# Pro_Trinket_Keyboard_V3_2.net
KiCad netlist of a schematic drawn in EAGLE
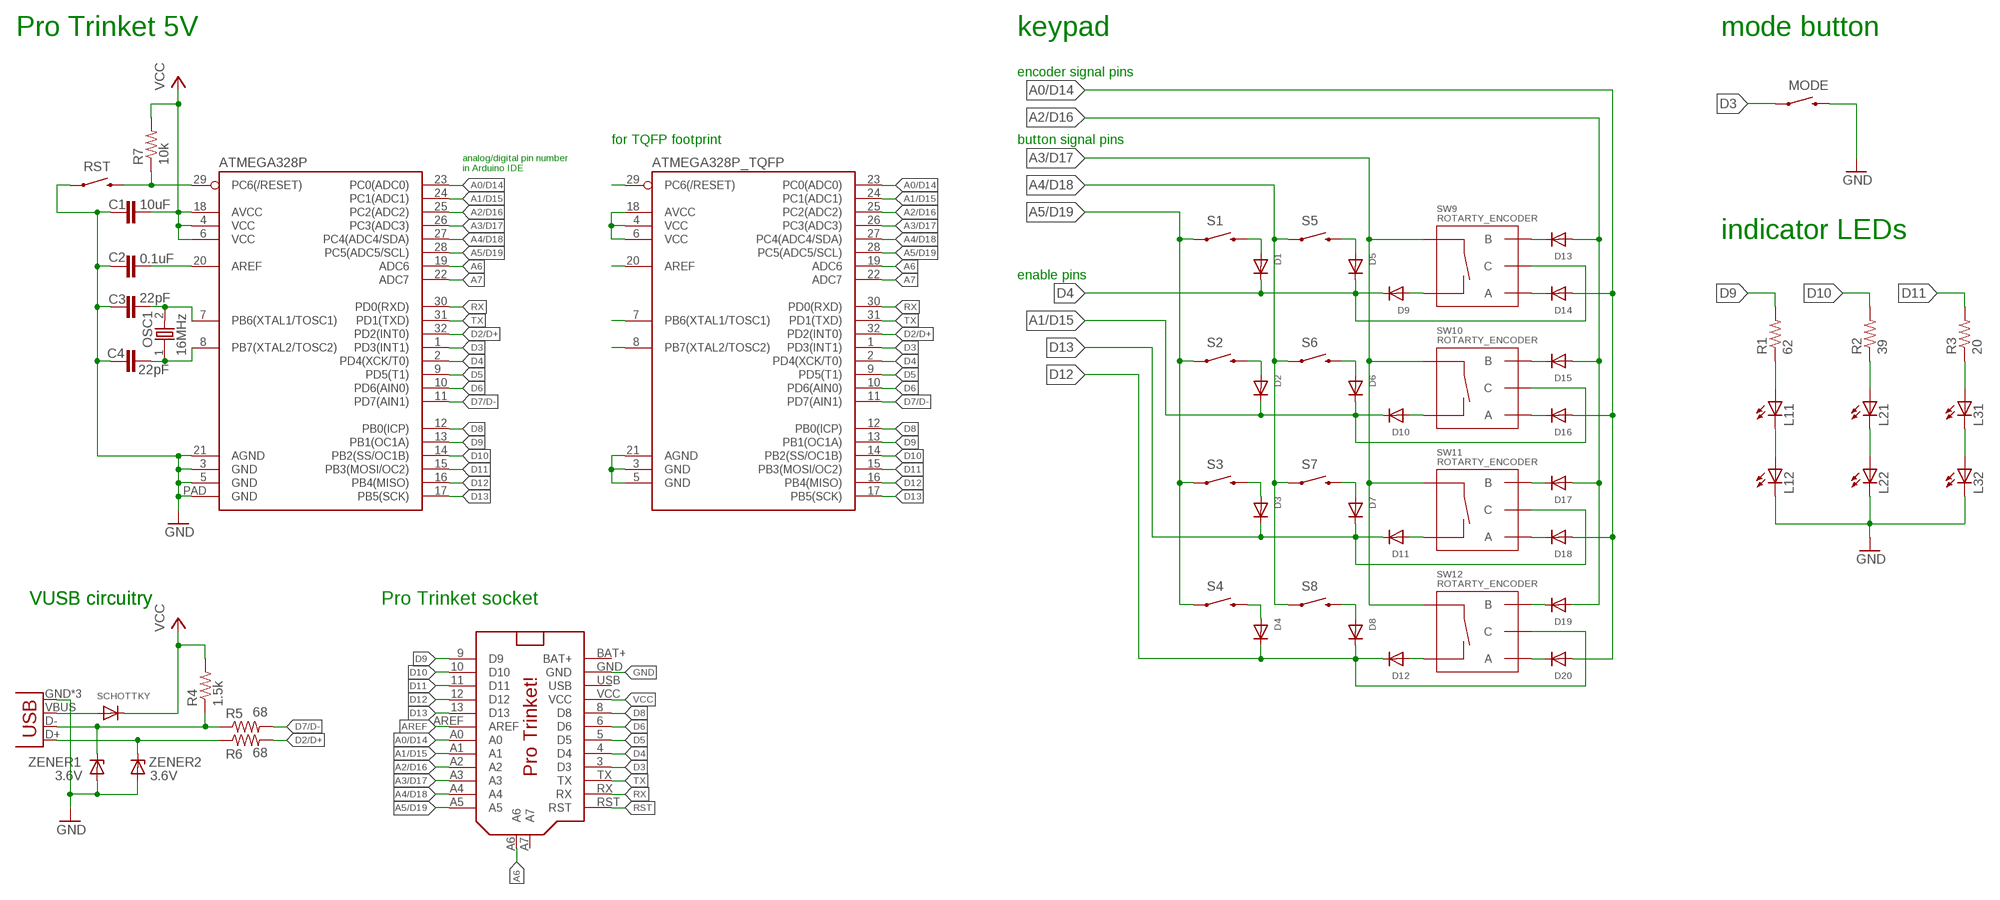
[diagram p0: schematic, sheet 1]

(export (version "E")
  (design (tool "Eeschema 10.0.6"))
  (components
    (comp (ref "ATMEGA328P")
      (value "ATMEGA328P_MLFMLF32")
      (footprint "eagle-import:MLF32-PAD")
      (libsource (lib "eagle-import") (part "ATMEGA328P_MLFMLF32"))
    )
    (comp (ref "ATMEGA328P_TQFP")
      (value "ATMEGA328P_TQFP")
      (footprint "eagle-import:TQFP32-08")
      (libsource (lib "eagle-import") (part "ATMEGA328P_TQFP"))
    )
    (comp (ref "C1")
      (value "10uF")
      (footprint "eagle-import:0603-CAP")
      (libsource (lib "eagle-import") (part "10UF-6.3V-20%(0603)"))
    )
    (comp (ref "C2")
      (value "0.1uF")
      (footprint "eagle-import:0603-CAP")
      (libsource (lib "eagle-import") (part "22PF-50V-5%(0603)"))
    )
    (comp (ref "C3")
      (value "22pF")
      (footprint "eagle-import:0603-CAP")
      (libsource (lib "eagle-import") (part "22PF-50V-5%(0603)"))
    )
    (comp (ref "C4")
      (value "22pF")
      (footprint "eagle-import:0603-CAP")
      (libsource (lib "eagle-import") (part "22PF-50V-5%(0603)"))
    )
    (comp (ref "D1")
      (value "DIODESOD-123")
      (footprint "eagle-import:SOD-123")
      (libsource (lib "eagle-import") (part "DIODESOD-123"))
    )
    (comp (ref "D2")
      (value "DIODESOD-123")
      (footprint "eagle-import:SOD-123")
      (libsource (lib "eagle-import") (part "DIODESOD-123"))
    )
    (comp (ref "D3")
      (value "DIODESOD-123")
      (footprint "eagle-import:SOD-123")
      (libsource (lib "eagle-import") (part "DIODESOD-123"))
    )
    (comp (ref "D4")
      (value "DIODESOD-123")
      (footprint "eagle-import:SOD-123")
      (libsource (lib "eagle-import") (part "DIODESOD-123"))
    )
    (comp (ref "D5")
      (value "DIODESOD-123")
      (footprint "eagle-import:SOD-123")
      (libsource (lib "eagle-import") (part "DIODESOD-123"))
    )
    (comp (ref "D6")
      (value "DIODESOD-123")
      (footprint "eagle-import:SOD-123")
      (libsource (lib "eagle-import") (part "DIODESOD-123"))
    )
    (comp (ref "D7")
      (value "DIODESOD-123")
      (footprint "eagle-import:SOD-123")
      (libsource (lib "eagle-import") (part "DIODESOD-123"))
    )
    (comp (ref "D8")
      (value "DIODESOD-123")
      (footprint "eagle-import:SOD-123")
      (libsource (lib "eagle-import") (part "DIODESOD-123"))
    )
    (comp (ref "D9")
      (value "DIODESOD-123")
      (footprint "eagle-import:SOD-123")
      (libsource (lib "eagle-import") (part "DIODESOD-123"))
    )
    (comp (ref "D10")
      (value "DIODESOD-123")
      (footprint "eagle-import:SOD-123")
      (libsource (lib "eagle-import") (part "DIODESOD-123"))
    )
    (comp (ref "D11")
      (value "DIODESOD-123")
      (footprint "eagle-import:SOD-123")
      (libsource (lib "eagle-import") (part "DIODESOD-123"))
    )
    (comp (ref "D12")
      (value "DIODESOD-123")
      (footprint "eagle-import:SOD-123")
      (libsource (lib "eagle-import") (part "DIODESOD-123"))
    )
    (comp (ref "D13")
      (value "DIODESOD-123")
      (footprint "eagle-import:SOD-123")
      (libsource (lib "eagle-import") (part "DIODESOD-123"))
    )
    (comp (ref "D14")
      (value "DIODESOD-123")
      (footprint "eagle-import:SOD-123")
      (libsource (lib "eagle-import") (part "DIODESOD-123"))
    )
    (comp (ref "D15")
      (value "DIODESOD-123")
      (footprint "eagle-import:SOD-123")
      (libsource (lib "eagle-import") (part "DIODESOD-123"))
    )
    (comp (ref "D16")
      (value "DIODESOD-123")
      (footprint "eagle-import:SOD-123")
      (libsource (lib "eagle-import") (part "DIODESOD-123"))
    )
    (comp (ref "D17")
      (value "DIODESOD-123")
      (footprint "eagle-import:SOD-123")
      (libsource (lib "eagle-import") (part "DIODESOD-123"))
    )
    (comp (ref "D18")
      (value "DIODESOD-123")
      (footprint "eagle-import:SOD-123")
      (libsource (lib "eagle-import") (part "DIODESOD-123"))
    )
    (comp (ref "D19")
      (value "DIODESOD-123")
      (footprint "eagle-import:SOD-123")
      (libsource (lib "eagle-import") (part "DIODESOD-123"))
    )
    (comp (ref "D20")
      (value "DIODESOD-123")
      (footprint "eagle-import:SOD-123")
      (libsource (lib "eagle-import") (part "DIODESOD-123"))
    )
    (comp (ref "JP1")
      (value "USB-MICROB")
      (footprint "eagle-import:USB-MICROB")
      (libsource (lib "eagle-import") (part "USB-MICROB"))
    )
    (comp (ref "L11")
      (value "LEDCHIPLED_0805")
      (footprint "eagle-import:CHIPLED_0805")
      (libsource (lib "eagle-import") (part "LEDCHIPLED_0805"))
    )
    (comp (ref "L12")
      (value "LEDCHIPLED_0805")
      (footprint "eagle-import:CHIPLED_0805")
      (libsource (lib "eagle-import") (part "LEDCHIPLED_0805"))
    )
    (comp (ref "L21")
      (value "LEDCHIPLED_0805")
      (footprint "eagle-import:CHIPLED_0805")
      (libsource (lib "eagle-import") (part "LEDCHIPLED_0805"))
    )
    (comp (ref "L22")
      (value "LEDCHIPLED_0805")
      (footprint "eagle-import:CHIPLED_0805")
      (libsource (lib "eagle-import") (part "LEDCHIPLED_0805"))
    )
    (comp (ref "L31")
      (value "LEDCHIPLED_0805")
      (footprint "eagle-import:CHIPLED_0805")
      (libsource (lib "eagle-import") (part "LEDCHIPLED_0805"))
    )
    (comp (ref "L32")
      (value "LEDCHIPLED_0805")
      (footprint "eagle-import:CHIPLED_0805")
      (libsource (lib "eagle-import") (part "LEDCHIPLED_0805"))
    )
    (comp (ref "MODE")
      (value "SWITCH-MOMENTARY-2SIDE_EZ")
      (footprint "eagle-import:TACTILE-PTH-SIDEEZ")
      (libsource (lib "eagle-import") (part "SWITCH-MOMENTARY-2SIDE_EZ"))
    )
    (comp (ref "OSC1")
      (value "16MHz")
      (footprint "eagle-import:HC-49U")
      (libsource (lib "eagle-import") (part "OSC-XTAL-HC-49U-SMD"))
    )
    (comp (ref "R1")
      (value "62")
      (footprint "eagle-import:M0805")
      (libsource (lib "eagle-import") (part "R-US_M0805"))
    )
    (comp (ref "R2")
      (value "39")
      (footprint "eagle-import:M0805")
      (libsource (lib "eagle-import") (part "R-US_M0805"))
    )
    (comp (ref "R3")
      (value "20")
      (footprint "eagle-import:M0805")
      (libsource (lib "eagle-import") (part "R-US_M0805"))
    )
    (comp (ref "R4")
      (value "1.5k")
      (footprint "eagle-import:0805")
      (libsource (lib "eagle-import") (part "RESISTOR0805-RES"))
    )
    (comp (ref "R5")
      (value "68")
      (footprint "eagle-import:0805")
      (libsource (lib "eagle-import") (part "RESISTOR0805-RES"))
    )
    (comp (ref "R6")
      (value "68")
      (footprint "eagle-import:0805")
      (libsource (lib "eagle-import") (part "RESISTOR0805-RES"))
    )
    (comp (ref "R7")
      (value "10k")
      (footprint "eagle-import:0805")
      (libsource (lib "eagle-import") (part "RESISTOR0805-RES"))
    )
    (comp (ref "RST")
      (value "SWITCH-MOMENTARY-2SIDE_EZ")
      (footprint "eagle-import:TACTILE-PTH-SIDEEZ")
      (libsource (lib "eagle-import") (part "SWITCH-MOMENTARY-2SIDE_EZ"))
    )
    (comp (ref "S1")
      (value "SWITCH-MOMENTARY-212MM")
      (footprint "eagle-import:TACTILE-PTH-12MM")
      (libsource (lib "eagle-import") (part "SWITCH-MOMENTARY-212MM"))
    )
    (comp (ref "S2")
      (value "SWITCH-MOMENTARY-212MM")
      (footprint "eagle-import:TACTILE-PTH-12MM")
      (libsource (lib "eagle-import") (part "SWITCH-MOMENTARY-212MM"))
    )
    (comp (ref "S3")
      (value "SWITCH-MOMENTARY-212MM")
      (footprint "eagle-import:TACTILE-PTH-12MM")
      (libsource (lib "eagle-import") (part "SWITCH-MOMENTARY-212MM"))
    )
    (comp (ref "S4")
      (value "SWITCH-MOMENTARY-212MM")
      (footprint "eagle-import:TACTILE-PTH-12MM")
      (libsource (lib "eagle-import") (part "SWITCH-MOMENTARY-212MM"))
    )
    (comp (ref "S5")
      (value "SWITCH-MOMENTARY-212MM")
      (footprint "eagle-import:TACTILE-PTH-12MM")
      (libsource (lib "eagle-import") (part "SWITCH-MOMENTARY-212MM"))
    )
    (comp (ref "S6")
      (value "SWITCH-MOMENTARY-212MM")
      (footprint "eagle-import:TACTILE-PTH-12MM")
      (libsource (lib "eagle-import") (part "SWITCH-MOMENTARY-212MM"))
    )
    (comp (ref "S7")
      (value "SWITCH-MOMENTARY-212MM")
      (footprint "eagle-import:TACTILE-PTH-12MM")
      (libsource (lib "eagle-import") (part "SWITCH-MOMENTARY-212MM"))
    )
    (comp (ref "S8")
      (value "SWITCH-MOMENTARY-212MM")
      (footprint "eagle-import:TACTILE-PTH-12MM")
      (libsource (lib "eagle-import") (part "SWITCH-MOMENTARY-212MM"))
    )
    (comp (ref "SCHOTTKY")
      (value "DIODESMA")
      (footprint "eagle-import:SMADIODE")
      (libsource (lib "eagle-import") (part "DIODESMA"))
    )
    (comp (ref "SW9")
      (value "ROTARTY_ENCODER")
      (footprint "eagle-import:ROTARY_ENC_PLAIN")
      (libsource (lib "eagle-import") (part "ROTARTY_ENCODER"))
    )
    (comp (ref "SW10")
      (value "ROTARTY_ENCODER")
      (footprint "eagle-import:ROTARY_ENC_PLAIN")
      (libsource (lib "eagle-import") (part "ROTARTY_ENCODER"))
    )
    (comp (ref "SW11")
      (value "ROTARTY_ENCODER")
      (footprint "eagle-import:ROTARY_ENC_PLAIN")
      (libsource (lib "eagle-import") (part "ROTARTY_ENCODER"))
    )
    (comp (ref "SW12")
      (value "ROTARTY_ENCODER")
      (footprint "eagle-import:ROTARY_ENC_PLAIN")
      (libsource (lib "eagle-import") (part "ROTARTY_ENCODER"))
    )
    (comp (ref "U$2")
      (value "PRO_TRINKET")
      (footprint "eagle-import:PROTRINKET")
      (libsource (lib "eagle-import") (part "PRO_TRINKET"))
    )
    (comp (ref "ZENER1")
      (value "3.6V")
      (footprint "eagle-import:SOD80C")
      (libsource (lib "eagle-import") (part "ZENER-DIODESOD80C"))
    )
    (comp (ref "ZENER2")
      (value "3.6V")
      (footprint "eagle-import:SOD80C")
      (libsource (lib "eagle-import") (part "ZENER-DIODESOD80C"))
    )
  )
  (nets
    (net (code "1") (name "/BAT+") (class "Default")
      (node (ref "U$2") (pin "BAT+") (pinfunction "BAT+_BAT+") (pintype "power_in"))
    )
    (net (code "2") (name "/USB") (class "Default")
      (node (ref "U$2") (pin "USB") (pinfunction "USB_USB") (pintype "power_in"))
    )
    (net (code "3") (name "/XTAL1") (class "Default")
      (node (ref "ATMEGA328P") (pin "7") (pinfunction "PB6(XTAL1/TOSC1)_7") (pintype "bidirectional"))
      (node (ref "ATMEGA328P_TQFP") (pin "7") (pinfunction "PB6(XTAL1/TOSC1)_7") (pintype "bidirectional"))
      (node (ref "C3") (pin "2") (pinfunction "2_2") (pintype "passive"))
      (node (ref "OSC1") (pin "2") (pinfunction "2_2") (pintype "passive"))
    )
    (net (code "4") (name "/XTAL2") (class "Default")
      (node (ref "ATMEGA328P") (pin "8") (pinfunction "PB7(XTAL2/TOSC2)_8") (pintype "bidirectional"))
      (node (ref "ATMEGA328P_TQFP") (pin "8") (pinfunction "PB7(XTAL2/TOSC2)_8") (pintype "bidirectional"))
      (node (ref "C4") (pin "1") (pinfunction "1_1") (pintype "passive"))
      (node (ref "OSC1") (pin "1") (pinfunction "1_1") (pintype "passive"))
    )
    (net (code "5") (name "A0{slash}D14") (class "Default")
      (node (ref "ATMEGA328P") (pin "23") (pinfunction "PC0(ADC0)_23") (pintype "bidirectional"))
      (node (ref "ATMEGA328P_TQFP") (pin "23") (pinfunction "PC0(ADC0)_23") (pintype "bidirectional"))
      (node (ref "D14") (pin "A") (pinfunction "A_A") (pintype "passive"))
      (node (ref "D16") (pin "A") (pinfunction "A_A") (pintype "passive"))
      (node (ref "D18") (pin "A") (pinfunction "A_A") (pintype "passive"))
      (node (ref "D20") (pin "A") (pinfunction "A_A") (pintype "passive"))
      (node (ref "U$2") (pin "A0") (pinfunction "A0_A0") (pintype "bidirectional"))
    )
    (net (code "6") (name "A1{slash}D15") (class "Default")
      (node (ref "ATMEGA328P") (pin "24") (pinfunction "PC1(ADC1)_24") (pintype "bidirectional"))
      (node (ref "ATMEGA328P_TQFP") (pin "24") (pinfunction "PC1(ADC1)_24") (pintype "bidirectional"))
      (node (ref "D10") (pin "C") (pinfunction "C_C") (pintype "passive"))
      (node (ref "D2") (pin "C") (pinfunction "C_C") (pintype "passive"))
      (node (ref "D6") (pin "C") (pinfunction "C_C") (pintype "passive"))
      (node (ref "SW10") (pin "C") (pinfunction "C_C") (pintype "bidirectional"))
      (node (ref "U$2") (pin "A1") (pinfunction "A1_A1") (pintype "bidirectional"))
    )
    (net (code "7") (name "A2{slash}D16") (class "Default")
      (node (ref "ATMEGA328P") (pin "25") (pinfunction "PC2(ADC2)_25") (pintype "bidirectional"))
      (node (ref "ATMEGA328P_TQFP") (pin "25") (pinfunction "PC2(ADC2)_25") (pintype "bidirectional"))
      (node (ref "D13") (pin "A") (pinfunction "A_A") (pintype "passive"))
      (node (ref "D15") (pin "A") (pinfunction "A_A") (pintype "passive"))
      (node (ref "D17") (pin "A") (pinfunction "A_A") (pintype "passive"))
      (node (ref "D19") (pin "A") (pinfunction "A_A") (pintype "passive"))
      (node (ref "U$2") (pin "A2") (pinfunction "A2_A2") (pintype "bidirectional"))
    )
    (net (code "8") (name "A3{slash}D17") (class "Default")
      (node (ref "ATMEGA328P") (pin "26") (pinfunction "PC3(ADC3)_26") (pintype "bidirectional"))
      (node (ref "ATMEGA328P_TQFP") (pin "26") (pinfunction "PC3(ADC3)_26") (pintype "bidirectional"))
      (node (ref "SW10") (pin "SW+") (pinfunction "SW+_SW+") (pintype "bidirectional"))
      (node (ref "SW11") (pin "SW+") (pinfunction "SW+_SW+") (pintype "bidirectional"))
      (node (ref "SW12") (pin "SW+") (pinfunction "SW+_SW+") (pintype "bidirectional"))
      (node (ref "SW9") (pin "SW+") (pinfunction "SW+_SW+") (pintype "bidirectional"))
      (node (ref "U$2") (pin "A3") (pinfunction "A3_A3") (pintype "bidirectional"))
    )
    (net (code "9") (name "A4{slash}D18") (class "Default")
      (node (ref "ATMEGA328P") (pin "27") (pinfunction "PC4(ADC4/SDA)_27") (pintype "bidirectional"))
      (node (ref "ATMEGA328P_TQFP") (pin "27") (pinfunction "PC4(ADC4/SDA)_27") (pintype "bidirectional"))
      (node (ref "S5") (pin "1") (pinfunction "1_1") (pintype "passive"))
      (node (ref "S5") (pin "2") (pinfunction "1_2") (pintype "passive"))
      (node (ref "S6") (pin "1") (pinfunction "1_1") (pintype "passive"))
      (node (ref "S6") (pin "2") (pinfunction "1_2") (pintype "passive"))
      (node (ref "S7") (pin "1") (pinfunction "1_1") (pintype "passive"))
      (node (ref "S7") (pin "2") (pinfunction "1_2") (pintype "passive"))
      (node (ref "S8") (pin "1") (pinfunction "1_1") (pintype "passive"))
      (node (ref "S8") (pin "2") (pinfunction "1_2") (pintype "passive"))
      (node (ref "U$2") (pin "A4") (pinfunction "A4_A4") (pintype "bidirectional"))
    )
    (net (code "10") (name "A5{slash}D19") (class "Default")
      (node (ref "ATMEGA328P") (pin "28") (pinfunction "PC5(ADC5/SCL)_28") (pintype "bidirectional"))
      (node (ref "ATMEGA328P_TQFP") (pin "28") (pinfunction "PC5(ADC5/SCL)_28") (pintype "bidirectional"))
      (node (ref "S1") (pin "1") (pinfunction "1_1") (pintype "passive"))
      (node (ref "S1") (pin "2") (pinfunction "1_2") (pintype "passive"))
      (node (ref "S2") (pin "1") (pinfunction "1_1") (pintype "passive"))
      (node (ref "S2") (pin "2") (pinfunction "1_2") (pintype "passive"))
      (node (ref "S3") (pin "1") (pinfunction "1_1") (pintype "passive"))
      (node (ref "S3") (pin "2") (pinfunction "1_2") (pintype "passive"))
      (node (ref "S4") (pin "1") (pinfunction "1_1") (pintype "passive"))
      (node (ref "S4") (pin "2") (pinfunction "1_2") (pintype "passive"))
      (node (ref "U$2") (pin "A5") (pinfunction "A5_A5") (pintype "bidirectional"))
    )
    (net (code "11") (name "A6") (class "Default")
      (node (ref "ATMEGA328P") (pin "19") (pinfunction "ADC6_19") (pintype "bidirectional"))
      (node (ref "ATMEGA328P_TQFP") (pin "19") (pinfunction "ADC6_19") (pintype "bidirectional"))
      (node (ref "U$2") (pin "A6") (pinfunction "A6_A6") (pintype "passive"))
    )
    (net (code "12") (name "A7") (class "Default")
      (node (ref "ATMEGA328P") (pin "22") (pinfunction "ADC7_22") (pintype "bidirectional"))
      (node (ref "ATMEGA328P_TQFP") (pin "22") (pinfunction "ADC7_22") (pintype "bidirectional"))
    )
    (net (code "13") (name "AREF") (class "Default")
      (node (ref "ATMEGA328P") (pin "20") (pinfunction "AREF_20") (pintype "bidirectional"))
      (node (ref "ATMEGA328P_TQFP") (pin "20") (pinfunction "AREF_20") (pintype "bidirectional"))
      (node (ref "C2") (pin "2") (pinfunction "2_2") (pintype "passive"))
      (node (ref "U$2") (pin "AREF") (pinfunction "AREF_AREF") (pintype "passive"))
    )
    (net (code "14") (name "D2{slash}D+") (class "Default")
      (node (ref "ATMEGA328P") (pin "32") (pinfunction "PD2(INT0)_32") (pintype "bidirectional"))
      (node (ref "ATMEGA328P_TQFP") (pin "32") (pinfunction "PD2(INT0)_32") (pintype "bidirectional"))
      (node (ref "R6") (pin "2") (pinfunction "2_2") (pintype "passive"))
    )
    (net (code "15") (name "D3") (class "Default")
      (node (ref "ATMEGA328P") (pin "1") (pinfunction "PD3(INT1)_1") (pintype "bidirectional"))
      (node (ref "ATMEGA328P_TQFP") (pin "1") (pinfunction "PD3(INT1)_1") (pintype "bidirectional"))
      (node (ref "MODE") (pin "1") (pinfunction "1_1") (pintype "passive"))
      (node (ref "U$2") (pin "3") (pinfunction "D3_3") (pintype "bidirectional"))
    )
    (net (code "16") (name "D4") (class "Default")
      (node (ref "ATMEGA328P") (pin "2") (pinfunction "PD4(XCK/T0)_2") (pintype "bidirectional"))
      (node (ref "ATMEGA328P_TQFP") (pin "2") (pinfunction "PD4(XCK/T0)_2") (pintype "bidirectional"))
      (node (ref "D1") (pin "C") (pinfunction "C_C") (pintype "passive"))
      (node (ref "D5") (pin "C") (pinfunction "C_C") (pintype "passive"))
      (node (ref "D9") (pin "C") (pinfunction "C_C") (pintype "passive"))
      (node (ref "SW9") (pin "C") (pinfunction "C_C") (pintype "bidirectional"))
      (node (ref "U$2") (pin "4") (pinfunction "D4_4") (pintype "bidirectional"))
    )
    (net (code "17") (name "D5") (class "Default")
      (node (ref "ATMEGA328P") (pin "9") (pinfunction "PD5(T1)_9") (pintype "bidirectional"))
      (node (ref "ATMEGA328P_TQFP") (pin "9") (pinfunction "PD5(T1)_9") (pintype "bidirectional"))
      (node (ref "U$2") (pin "5") (pinfunction "D5_5") (pintype "bidirectional"))
    )
    (net (code "18") (name "D6") (class "Default")
      (node (ref "ATMEGA328P") (pin "10") (pinfunction "PD6(AIN0)_10") (pintype "bidirectional"))
      (node (ref "ATMEGA328P_TQFP") (pin "10") (pinfunction "PD6(AIN0)_10") (pintype "bidirectional"))
      (node (ref "U$2") (pin "6") (pinfunction "D6_6") (pintype "bidirectional"))
    )
    (net (code "19") (name "D7{slash}D-") (class "Default")
      (node (ref "ATMEGA328P") (pin "11") (pinfunction "PD7(AIN1)_11") (pintype "bidirectional"))
      (node (ref "ATMEGA328P_TQFP") (pin "11") (pinfunction "PD7(AIN1)_11") (pintype "bidirectional"))
      (node (ref "R5") (pin "2") (pinfunction "2_2") (pintype "passive"))
    )
    (net (code "20") (name "D8") (class "Default")
      (node (ref "ATMEGA328P") (pin "12") (pinfunction "PB0(ICP)_12") (pintype "bidirectional"))
      (node (ref "ATMEGA328P_TQFP") (pin "12") (pinfunction "PB0(ICP)_12") (pintype "bidirectional"))
      (node (ref "U$2") (pin "8") (pinfunction "D8_8") (pintype "bidirectional"))
    )
    (net (code "21") (name "D9") (class "Default")
      (node (ref "ATMEGA328P") (pin "13") (pinfunction "PB1(OC1A)_13") (pintype "bidirectional"))
      (node (ref "ATMEGA328P_TQFP") (pin "13") (pinfunction "PB1(OC1A)_13") (pintype "bidirectional"))
      (node (ref "R1") (pin "2") (pinfunction "2_2") (pintype "passive"))
      (node (ref "U$2") (pin "9") (pinfunction "D9_9") (pintype "bidirectional"))
    )
    (net (code "22") (name "D10") (class "Default")
      (node (ref "ATMEGA328P") (pin "14") (pinfunction "PB2(SS/OC1B)_14") (pintype "bidirectional"))
      (node (ref "ATMEGA328P_TQFP") (pin "14") (pinfunction "PB2(SS/OC1B)_14") (pintype "bidirectional"))
      (node (ref "R2") (pin "2") (pinfunction "2_2") (pintype "passive"))
      (node (ref "U$2") (pin "10") (pinfunction "D10_10") (pintype "bidirectional"))
    )
    (net (code "23") (name "D11") (class "Default")
      (node (ref "ATMEGA328P") (pin "15") (pinfunction "PB3(MOSI/OC2)_15") (pintype "bidirectional"))
      (node (ref "ATMEGA328P_TQFP") (pin "15") (pinfunction "PB3(MOSI/OC2)_15") (pintype "bidirectional"))
      (node (ref "R3") (pin "2") (pinfunction "2_2") (pintype "passive"))
      (node (ref "U$2") (pin "11") (pinfunction "D11_11") (pintype "bidirectional"))
    )
    (net (code "24") (name "D12") (class "Default")
      (node (ref "ATMEGA328P") (pin "16") (pinfunction "PB4(MISO)_16") (pintype "bidirectional"))
      (node (ref "ATMEGA328P_TQFP") (pin "16") (pinfunction "PB4(MISO)_16") (pintype "bidirectional"))
      (node (ref "D12") (pin "C") (pinfunction "C_C") (pintype "passive"))
      (node (ref "D4") (pin "C") (pinfunction "C_C") (pintype "passive"))
      (node (ref "D8") (pin "C") (pinfunction "C_C") (pintype "passive"))
      (node (ref "SW12") (pin "C") (pinfunction "C_C") (pintype "bidirectional"))
      (node (ref "U$2") (pin "12") (pinfunction "D12_12") (pintype "bidirectional"))
    )
    (net (code "25") (name "D13") (class "Default")
      (node (ref "ATMEGA328P") (pin "17") (pinfunction "PB5(SCK)_17") (pintype "bidirectional"))
      (node (ref "ATMEGA328P_TQFP") (pin "17") (pinfunction "PB5(SCK)_17") (pintype "bidirectional"))
      (node (ref "D11") (pin "C") (pinfunction "C_C") (pintype "passive"))
      (node (ref "D3") (pin "C") (pinfunction "C_C") (pintype "passive"))
      (node (ref "D7") (pin "C") (pinfunction "C_C") (pintype "passive"))
      (node (ref "SW11") (pin "C") (pinfunction "C_C") (pintype "bidirectional"))
      (node (ref "U$2") (pin "13") (pinfunction "D13_13") (pintype "bidirectional"))
    )
    (net (code "26") (name "GND") (class "Default")
      (node (ref "ATMEGA328P") (pin "21") (pinfunction "AGND_21") (pintype "bidirectional"))
      (node (ref "ATMEGA328P") (pin "3") (pinfunction "GND_3") (pintype "bidirectional"))
      (node (ref "ATMEGA328P") (pin "5") (pinfunction "GND_5") (pintype "bidirectional"))
      (node (ref "ATMEGA328P") (pin "PAD") (pinfunction "GND_PAD") (pintype "bidirectional"))
      (node (ref "ATMEGA328P_TQFP") (pin "21") (pinfunction "AGND_21") (pintype "bidirectional"))
      (node (ref "ATMEGA328P_TQFP") (pin "3") (pinfunction "GND_3") (pintype "bidirectional"))
      (node (ref "ATMEGA328P_TQFP") (pin "5") (pinfunction "GND_5") (pintype "bidirectional"))
      (node (ref "C1") (pin "1") (pinfunction "1_1") (pintype "passive"))
      (node (ref "C2") (pin "1") (pinfunction "1_1") (pintype "passive"))
      (node (ref "C3") (pin "1") (pinfunction "1_1") (pintype "passive"))
      (node (ref "C4") (pin "2") (pinfunction "2_2") (pintype "passive"))
      (node (ref "JP1") (pin "GND") (pinfunction "GND_GND") (pintype "bidirectional"))
      (node (ref "JP1") (pin "MT1") (pinfunction "GND_MT1") (pintype "bidirectional"))
      (node (ref "JP1") (pin "MT2") (pinfunction "GND_MT2") (pintype "bidirectional"))
      (node (ref "L12") (pin "C") (pinfunction "C_C") (pintype "passive"))
      (node (ref "L22") (pin "C") (pinfunction "C_C") (pintype "passive"))
      (node (ref "L32") (pin "C") (pinfunction "C_C") (pintype "passive"))
      (node (ref "MODE") (pin "2") (pinfunction "2_2") (pintype "passive"))
      (node (ref "RST") (pin "1") (pinfunction "1_1") (pintype "passive"))
      (node (ref "U$2") (pin "GND") (pinfunction "GND_GND") (pintype "power_in"))
      (node (ref "ZENER1") (pin "A") (pinfunction "A_A") (pintype "passive"))
      (node (ref "ZENER2") (pin "A") (pinfunction "A_A") (pintype "passive"))
    )
    (net (code "27") (name "Net-(D1-PadA)") (class "Default")
      (node (ref "D1") (pin "A") (pinfunction "A_A") (pintype "passive"))
      (node (ref "S1") (pin "3") (pinfunction "2_3") (pintype "passive"))
      (node (ref "S1") (pin "4") (pinfunction "2_4") (pintype "passive"))
    )
    (net (code "28") (name "Net-(D2-PadA)") (class "Default")
      (node (ref "D2") (pin "A") (pinfunction "A_A") (pintype "passive"))
      (node (ref "S2") (pin "3") (pinfunction "2_3") (pintype "passive"))
      (node (ref "S2") (pin "4") (pinfunction "2_4") (pintype "passive"))
    )
    (net (code "29") (name "Net-(D3-PadA)") (class "Default")
      (node (ref "D3") (pin "A") (pinfunction "A_A") (pintype "passive"))
      (node (ref "S3") (pin "3") (pinfunction "2_3") (pintype "passive"))
      (node (ref "S3") (pin "4") (pinfunction "2_4") (pintype "passive"))
    )
    (net (code "30") (name "Net-(D4-PadA)") (class "Default")
      (node (ref "D4") (pin "A") (pinfunction "A_A") (pintype "passive"))
      (node (ref "S4") (pin "3") (pinfunction "2_3") (pintype "passive"))
      (node (ref "S4") (pin "4") (pinfunction "2_4") (pintype "passive"))
    )
    (net (code "31") (name "Net-(D5-PadA)") (class "Default")
      (node (ref "D5") (pin "A") (pinfunction "A_A") (pintype "passive"))
      (node (ref "S5") (pin "3") (pinfunction "2_3") (pintype "passive"))
      (node (ref "S5") (pin "4") (pinfunction "2_4") (pintype "passive"))
    )
    (net (code "32") (name "Net-(D6-PadA)") (class "Default")
      (node (ref "D6") (pin "A") (pinfunction "A_A") (pintype "passive"))
      (node (ref "S6") (pin "3") (pinfunction "2_3") (pintype "passive"))
      (node (ref "S6") (pin "4") (pinfunction "2_4") (pintype "passive"))
    )
    (net (code "33") (name "Net-(D7-PadA)") (class "Default")
      (node (ref "D7") (pin "A") (pinfunction "A_A") (pintype "passive"))
      (node (ref "S7") (pin "3") (pinfunction "2_3") (pintype "passive"))
      (node (ref "S7") (pin "4") (pinfunction "2_4") (pintype "passive"))
    )
    (net (code "34") (name "Net-(D8-PadA)") (class "Default")
      (node (ref "D8") (pin "A") (pinfunction "A_A") (pintype "passive"))
      (node (ref "S8") (pin "3") (pinfunction "2_3") (pintype "passive"))
      (node (ref "S8") (pin "4") (pinfunction "2_4") (pintype "passive"))
    )
    (net (code "35") (name "Net-(D9-PadA)") (class "Default")
      (node (ref "D9") (pin "A") (pinfunction "A_A") (pintype "passive"))
      (node (ref "SW9") (pin "SW-") (pinfunction "SW-_SW-") (pintype "bidirectional"))
    )
    (net (code "36") (name "Net-(D10-PadA)") (class "Default")
      (node (ref "D10") (pin "A") (pinfunction "A_A") (pintype "passive"))
      (node (ref "SW10") (pin "SW-") (pinfunction "SW-_SW-") (pintype "bidirectional"))
    )
    (net (code "37") (name "Net-(D11-PadA)") (class "Default")
      (node (ref "D11") (pin "A") (pinfunction "A_A") (pintype "passive"))
      (node (ref "SW11") (pin "SW-") (pinfunction "SW-_SW-") (pintype "bidirectional"))
    )
    (net (code "38") (name "Net-(D12-PadA)") (class "Default")
      (node (ref "D12") (pin "A") (pinfunction "A_A") (pintype "passive"))
      (node (ref "SW12") (pin "SW-") (pinfunction "SW-_SW-") (pintype "bidirectional"))
    )
    (net (code "39") (name "Net-(D13-PadC)") (class "Default")
      (node (ref "D13") (pin "C") (pinfunction "C_C") (pintype "passive"))
      (node (ref "SW9") (pin "B") (pinfunction "B_B") (pintype "bidirectional"))
    )
    (net (code "40") (name "Net-(D14-PadC)") (class "Default")
      (node (ref "D14") (pin "C") (pinfunction "C_C") (pintype "passive"))
      (node (ref "SW9") (pin "A") (pinfunction "A_A") (pintype "bidirectional"))
    )
    (net (code "41") (name "Net-(D15-PadC)") (class "Default")
      (node (ref "D15") (pin "C") (pinfunction "C_C") (pintype "passive"))
      (node (ref "SW10") (pin "B") (pinfunction "B_B") (pintype "bidirectional"))
    )
    (net (code "42") (name "Net-(D16-PadC)") (class "Default")
      (node (ref "D16") (pin "C") (pinfunction "C_C") (pintype "passive"))
      (node (ref "SW10") (pin "A") (pinfunction "A_A") (pintype "bidirectional"))
    )
    (net (code "43") (name "Net-(D17-PadC)") (class "Default")
      (node (ref "D17") (pin "C") (pinfunction "C_C") (pintype "passive"))
      (node (ref "SW11") (pin "B") (pinfunction "B_B") (pintype "bidirectional"))
    )
    (net (code "44") (name "Net-(D18-PadC)") (class "Default")
      (node (ref "D18") (pin "C") (pinfunction "C_C") (pintype "passive"))
      (node (ref "SW11") (pin "A") (pinfunction "A_A") (pintype "bidirectional"))
    )
    (net (code "45") (name "Net-(D19-PadC)") (class "Default")
      (node (ref "D19") (pin "C") (pinfunction "C_C") (pintype "passive"))
      (node (ref "SW12") (pin "B") (pinfunction "B_B") (pintype "bidirectional"))
    )
    (net (code "46") (name "Net-(D20-PadC)") (class "Default")
      (node (ref "D20") (pin "C") (pinfunction "C_C") (pintype "passive"))
      (node (ref "SW12") (pin "A") (pinfunction "A_A") (pintype "bidirectional"))
    )
    (net (code "47") (name "Net-(JP1-PadD+)") (class "Default")
      (node (ref "JP1") (pin "D+") (pinfunction "D+_D+") (pintype "bidirectional"))
      (node (ref "R6") (pin "1") (pinfunction "1_1") (pintype "passive"))
      (node (ref "ZENER2") (pin "C") (pinfunction "C_C") (pintype "passive"))
    )
    (net (code "48") (name "Net-(JP1-PadD-)") (class "Default")
      (node (ref "JP1") (pin "D-") (pinfunction "D-_D-") (pintype "bidirectional"))
      (node (ref "R4") (pin "1") (pinfunction "1_1") (pintype "passive"))
      (node (ref "R5") (pin "1") (pinfunction "1_1") (pintype "passive"))
      (node (ref "ZENER1") (pin "C") (pinfunction "C_C") (pintype "passive"))
    )
    (net (code "49") (name "Net-(JP1-PadVBUS)") (class "Default")
      (node (ref "JP1") (pin "VBUS") (pinfunction "VBUS_VBUS") (pintype "bidirectional"))
      (node (ref "SCHOTTKY") (pin "A") (pinfunction "A_A") (pintype "passive"))
    )
    (net (code "50") (name "Net-(L11-PadA)") (class "Default")
      (node (ref "L11") (pin "A") (pinfunction "A_A") (pintype "passive"))
      (node (ref "R1") (pin "1") (pinfunction "1_1") (pintype "passive"))
    )
    (net (code "51") (name "Net-(L11-PadC)") (class "Default")
      (node (ref "L11") (pin "C") (pinfunction "C_C") (pintype "passive"))
      (node (ref "L12") (pin "A") (pinfunction "A_A") (pintype "passive"))
    )
    (net (code "52") (name "Net-(L21-PadA)") (class "Default")
      (node (ref "L21") (pin "A") (pinfunction "A_A") (pintype "passive"))
      (node (ref "R2") (pin "1") (pinfunction "1_1") (pintype "passive"))
    )
    (net (code "53") (name "Net-(L21-PadC)") (class "Default")
      (node (ref "L21") (pin "C") (pinfunction "C_C") (pintype "passive"))
      (node (ref "L22") (pin "A") (pinfunction "A_A") (pintype "passive"))
    )
    (net (code "54") (name "Net-(L31-PadA)") (class "Default")
      (node (ref "L31") (pin "A") (pinfunction "A_A") (pintype "passive"))
      (node (ref "R3") (pin "1") (pinfunction "1_1") (pintype "passive"))
    )
    (net (code "55") (name "Net-(L31-PadC)") (class "Default")
      (node (ref "L31") (pin "C") (pinfunction "C_C") (pintype "passive"))
      (node (ref "L32") (pin "A") (pinfunction "A_A") (pintype "passive"))
    )
    (net (code "56") (name "RST") (class "Default")
      (node (ref "ATMEGA328P") (pin "29") (pinfunction "PC6(/RESET)_29") (pintype "bidirectional"))
      (node (ref "ATMEGA328P_TQFP") (pin "29") (pinfunction "PC6(/RESET)_29") (pintype "bidirectional"))
      (node (ref "R7") (pin "1") (pinfunction "1_1") (pintype "passive"))
      (node (ref "RST") (pin "2") (pinfunction "2_2") (pintype "passive"))
      (node (ref "U$2") (pin "RST") (pinfunction "RST_RST") (pintype "passive"))
    )
    (net (code "57") (name "RX") (class "Default")
      (node (ref "ATMEGA328P") (pin "30") (pinfunction "PD0(RXD)_30") (pintype "bidirectional"))
      (node (ref "ATMEGA328P_TQFP") (pin "30") (pinfunction "PD0(RXD)_30") (pintype "bidirectional"))
      (node (ref "U$2") (pin "RX") (pinfunction "RX_RX") (pintype "bidirectional"))
    )
    (net (code "58") (name "TX") (class "Default")
      (node (ref "ATMEGA328P") (pin "31") (pinfunction "PD1(TXD)_31") (pintype "bidirectional"))
      (node (ref "ATMEGA328P_TQFP") (pin "31") (pinfunction "PD1(TXD)_31") (pintype "bidirectional"))
      (node (ref "U$2") (pin "TX") (pinfunction "TX_TX") (pintype "bidirectional"))
    )
    (net (code "59") (name "VCC") (class "Default")
      (node (ref "ATMEGA328P") (pin "18") (pinfunction "AVCC_18") (pintype "bidirectional"))
      (node (ref "ATMEGA328P") (pin "4") (pinfunction "VCC_4") (pintype "bidirectional"))
      (node (ref "ATMEGA328P") (pin "6") (pinfunction "VCC_6") (pintype "bidirectional"))
      (node (ref "ATMEGA328P_TQFP") (pin "18") (pinfunction "AVCC_18") (pintype "bidirectional"))
      (node (ref "ATMEGA328P_TQFP") (pin "4") (pinfunction "VCC_4") (pintype "bidirectional"))
      (node (ref "ATMEGA328P_TQFP") (pin "6") (pinfunction "VCC_6") (pintype "bidirectional"))
      (node (ref "C1") (pin "2") (pinfunction "2_2") (pintype "passive"))
      (node (ref "R4") (pin "2") (pinfunction "2_2") (pintype "passive"))
      (node (ref "R7") (pin "2") (pinfunction "2_2") (pintype "passive"))
      (node (ref "SCHOTTKY") (pin "C") (pinfunction "C_C") (pintype "passive"))
      (node (ref "U$2") (pin "VCC") (pinfunction "VCC_VCC") (pintype "power_in"))
    )
    (net (code "60") (name "unconnected-(U$2-PadA7)") (class "Default")
      (node (ref "U$2") (pin "A7") (pinfunction "A7_A7") (pintype "passive"))
    )
  )
)
